# Microcontroller_and_UI.net
KiCad netlist of a schematic drawn in Altium Designer
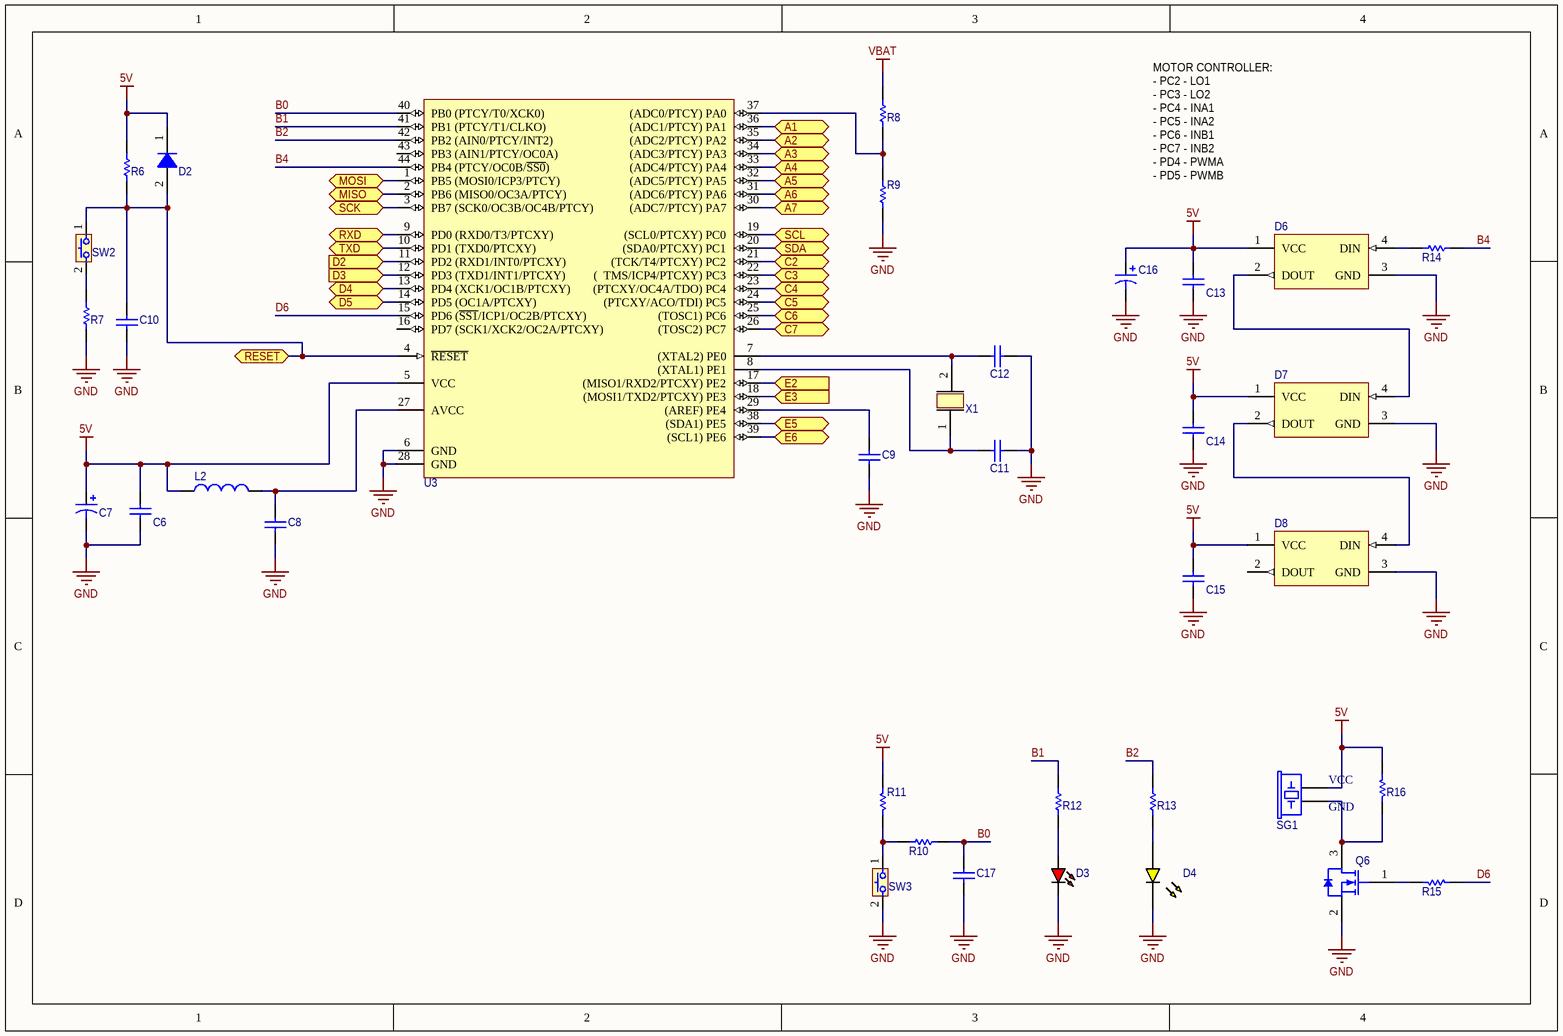
[diagram p0: Microcontroller and UI.SchDoc]

(export (version "E")
  (design (tool "Eeschema 10.0.6"))
  (components
    (comp (ref "C6")
      (value "Kemet C1206C104K5RACAUTO")
      (footprint "CAPC3216X88X50ML20T25")
      (description "Cap Ceramic 0.1uF 50V X7R 10% SMD 1206 125C Plastic T/R")
      (fields (field (name "MANUFACTURER PART NUMBER") "C1206C104K5RACAUTO"))
      (libsource (lib "Octopart library") (part "CAP-2"))
    )
    (comp (ref "C7")
      (value "Cap Pol2")
      (footprint "PCB-2utroa4rb2vd9is4ckmk-1")
      (description "Cap Tant 10UF 10% 16V 2312")
      (libsource (lib "Octopart library") (part "SYM-bf7b7726339260bc-1"))
    )
    (comp (ref "C8")
      (value "Kemet C1206C104K5RACAUTO")
      (footprint "CAPC3216X88X50ML20T25")
      (description "Cap Ceramic 0.1uF 50V X7R 10% SMD 1206 125C Plastic T/R")
      (fields (field (name "MANUFACTURER PART NUMBER") "C1206C104K5RACAUTO"))
      (libsource (lib "CommunityVault") (part "CAP-2"))
    )
    (comp (ref "C9")
      (value "Kemet C1206C104K5RACAUTO")
      (footprint "CAPC3216X88X50ML20T25")
      (description "Cap Ceramic 0.1uF 50V X7R 10% SMD 1206 125C Plastic T/R")
      (fields (field (name "MANUFACTURER PART NUMBER") "C1206C104K5RACAUTO"))
      (libsource (lib "CommunityVault") (part "CAP-2"))
    )
    (comp (ref "C10")
      (value "Kemet C1206C104K5RACAUTO")
      (footprint "CAPC3216X88X50ML20T25")
      (description "Cap Ceramic 0.1uF 50V X7R 10% SMD 1206 125C Plastic T/R")
      (fields (field (name "MANUFACTURER PART NUMBER") "C1206C104K5RACAUTO"))
      (libsource (lib "CommunityVault") (part "CAP-2"))
    )
    (comp (ref "C11")
      (value "Kemet C1206C220K5GACTU")
      (footprint "CAPC3216X88X50LL20T25")
      (fields (field (name "MANUFACTURER PART NUMBER") "C1206C220K5GACTU"))
      (libsource (lib "Octopart library") (part "CAP-2"))
    )
    (comp (ref "C12")
      (value "Kemet C1206C220K5GACTU")
      (footprint "CAPC3216X88X50LL20T25")
      (fields (field (name "MANUFACTURER PART NUMBER") "C1206C220K5GACTU"))
      (libsource (lib "Octopart library") (part "CAP-2"))
    )
    (comp (ref "C13")
      (value "Kemet C1206C104K5RACAUTO")
      (footprint "CAPC3216X88X50ML20T25")
      (description "Cap Ceramic 0.1uF 50V X7R 10% SMD 1206 125C Plastic T/R")
      (fields (field (name "MANUFACTURER PART NUMBER") "C1206C104K5RACAUTO"))
      (libsource (lib "CommunityVault") (part "CAP-2"))
    )
    (comp (ref "C14")
      (value "Kemet C1206C104K5RACAUTO")
      (footprint "CAPC3216X88X50ML20T25")
      (description "Cap Ceramic 0.1uF 50V X7R 10% SMD 1206 125C Plastic T/R")
      (fields (field (name "MANUFACTURER PART NUMBER") "C1206C104K5RACAUTO"))
      (libsource (lib "CommunityVault") (part "CAP-2"))
    )
    (comp (ref "C15")
      (value "Kemet C1206C104K5RACAUTO")
      (footprint "CAPC3216X88X50ML20T25")
      (description "Cap Ceramic 0.1uF 50V X7R 10% SMD 1206 125C Plastic T/R")
      (fields (field (name "MANUFACTURER PART NUMBER") "C1206C104K5RACAUTO"))
      (libsource (lib "CommunityVault") (part "CAP-2"))
    )
    (comp (ref "C16")
      (value "Panasonic EEEFK1C101P")
      (footprint "PCB-bxqn8ynar2jwyklg28q2-1")
      (description "Cap Aluminum Lytic 100uF 16V 20% (6.3 X 5.8mm) SMD 240mA 2000h 105°C Automotive T/R")
      (fields (field (name "MANUFACTURER PART NUMBER") "EEEFK1C101P"))
      (libsource (lib "Octopart library") (part "SYM-6d97a4db90fcb250-1"))
    )
    (comp (ref "C17")
      (value "Kemet C1206C104K5RACAUTO")
      (footprint "CAPC3216X88X50ML20T25")
      (description "Cap Ceramic 0.1uF 50V X7R 10% SMD 1206 125C Plastic T/R")
      (fields (field (name "MANUFACTURER PART NUMBER") "C1206C104K5RACAUTO"))
      (libsource (lib "CommunityVault") (part "CAP-2"))
    )
    (comp (ref "D2")
      (value "Fairchild Semiconductor FDLL4148")
      (footprint "LL-34_AP455")
      (description "Fairchild")
      (fields (field (name "MANUFACTURER PART NUMBER") "FDLL4148"))
      (libsource (lib "Octopart library") (part "DIODE-C1A2-2"))
    )
    (comp (ref "D3")
      (value "Lite-On LTST-C170KRKT")
      (footprint "PCB-7utjwvdtdw1v8scx5ylt-1")
      (description "Red 2 x 1.25 x 1.1 mm 130° Water Clear 54 mcd 2 V LED Surface Mount")
      (fields (field (name "MANUFACTURER PART NUMBER") "LTST-C170KRKT"))
      (libsource (lib "Octopart library") (part "SYM-1d24d4265bb4c2e3-2"))
    )
    (comp (ref "D4")
      (value "Lite-On LTST-C170KSKT")
      (footprint "PCB-3srso9uc5heegaq4ztu4-1")
      (description "Yellow 2 x 1.25 x 1.1 mm 130° Water Clear 112 mcd 1.8 V LED Surface Mount")
      (libsource (lib "Octopart library") (part "SYM-053ccc3e43addafb-1"))
    )
    (comp (ref "D6")
      (value "TE-1981584-1")
      (footprint "PCB-20395447-2")
      (description "INTELLIGENT CONTROL LED without centered Pad")
      (libsource (lib "Octopart library") (part "TE-1981584-1"))
    )
    (comp (ref "D7")
      (value "TE-1981584-1")
      (footprint "PCB-20395447-2")
      (description "INTELLIGENT CONTROL LED without centered Pad")
      (libsource (lib "Octopart library") (part "TE-1981584-1"))
    )
    (comp (ref "D8")
      (value "TE-1981584-1")
      (footprint "PCB-20395447-2")
      (description "INTELLIGENT CONTROL LED without centered Pad")
      (libsource (lib "Octopart library") (part "TE-1981584-1"))
    )
    (comp (ref "L2")
      (value "Bourns CM453232-100KL")
      (footprint "PCB-sj0d1m6kkfqzu57ryeks-1")
      (fields (field (name "MANUFACTURER PART NUMBER") "CM453232-100KL"))
      (libsource (lib "Octopart library") (part "SYM-f812311a91b727d5-1"))
    )
    (comp (ref "Q6")
      (value "SYM-ec4d21f6be82338a-2")
      (footprint "PCB-fnvh88uh0gwuonmuoobt-1")
      (fields (field (name "MANUFACTURER PART NUMBER") "BSS138P,215"))
      (libsource (lib "Octopart library") (part "SYM-ec4d21f6be82338a-2"))
    )
    (comp (ref "R6")
      (value "Vishay CRCW12064K70FKEA")
      (footprint "1206")
      (description "RES SMD 4.7K OHM 1% 1/4W 1206")
      (fields (field (name "MANUFACTURER PART NUMBER") "CRCW12064K70FKEA"))
      (libsource (lib "Octopart library") (part "CRCW12064K70FKEA"))
    )
    (comp (ref "R7")
      (value "Vishay CRCW1206330RFKEA")
      (footprint "PCB-iffx3kyo1buszuhrbsyd-1")
      (description "Res RES SMD 330 OHM 1% 1/4W 1206")
      (libsource (lib "Octopart library") (part "SYM-5f6d9438d73080aa-2"))
    )
    (comp (ref "R8")
      (value "Vishay CRCW12064K70FKEA")
      (footprint "1206")
      (description "RES SMD 4.7K OHM 1% 1/4W 1206")
      (fields (field (name "MANUFACTURER PART NUMBER") "CRCW12064K70FKEA"))
      (libsource (lib "Octopart library") (part "CRCW12064K70FKEA"))
    )
    (comp (ref "R9")
      (value "Vishay Dale CRCW12067K50FKTA")
      (footprint "RESC3216X60X45ML10T20")
      (description "RES SMD 7.5K OHM 1% 1/4W 1206")
      (fields (field (name "MANUFACTURER PART NUMBER") "CRCW12067K50FKTA"))
      (libsource (lib "Octopart library") (part "RES-2"))
    )
    (comp (ref "R10")
      (value "Vishay Dale CRCW12061K00FKEB")
      (footprint "RESC3216X60X45ML10T20")
      (description "Thick Film Resistors - SMD 1/4watt 1Kohms 1%")
      (fields (field (name "MANUFACTURER PART NUMBER") "CRCW12061K00FKEB"))
      (libsource (lib "Octopart library") (part "RES-2"))
    )
    (comp (ref "R11")
      (value "Res1")
      (footprint "PCB-r93x9swl7vzrlon1kcic-1")
      (description "Res Thick Film 1206 10K Ohm 1% 1/4W ±100ppm/°C Molded SMD SMD Paper T/R")
      (fields (field (name "MANUFACTURER PART NUMBER") "CRCW120610K0FKTA"))
      (libsource (lib "Octopart library") (part "SYM-1d37d65bd2a0c2f0-1"))
    )
    (comp (ref "R12")
      (value "Vishay Dale CRCW12061K00FKEB")
      (footprint "RESC3216X60X45ML10T20")
      (description "Thick Film Resistors - SMD 1/4watt 1Kohms 1%")
      (fields (field (name "MANUFACTURER PART NUMBER") "CRCW12061K00FKEB"))
      (libsource (lib "Octopart library") (part "RES-2"))
    )
    (comp (ref "R13")
      (value "Vishay Dale CRCW12061K00FKEB")
      (footprint "RESC3216X60X45ML10T20")
      (description "Thick Film Resistors - SMD 1/4watt 1Kohms 1%")
      (fields (field (name "MANUFACTURER PART NUMBER") "CRCW12061K00FKEB"))
      (libsource (lib "Octopart library") (part "RES-2"))
    )
    (comp (ref "R14")
      (value "Vishay CRCW1206330RFKEA")
      (footprint "PCB-iffx3kyo1buszuhrbsyd-1")
      (description "Res RES SMD 330 OHM 1% 1/4W 1206")
      (libsource (lib "Octopart library") (part "SYM-5f6d9438d73080aa-2"))
    )
    (comp (ref "R15")
      (value "Res1")
      (footprint "PCB-r93x9swl7vzrlon1kcic-1")
      (description "Res Thick Film 1206 10K Ohm 1% 1/4W ±100ppm/°C Molded SMD SMD Paper T/R")
      (fields (field (name "MANUFACTURER PART NUMBER") "CRCW120610K0FKTA"))
      (libsource (lib "Octopart library") (part "SYM-1d37d65bd2a0c2f0-1"))
    )
    (comp (ref "R16")
      (value "Res1")
      (footprint "PCB-r93x9swl7vzrlon1kcic-1")
      (description "Res Thick Film 1206 10K Ohm 1% 1/4W ±100ppm/°C Molded SMD SMD Paper T/R")
      (fields (field (name "MANUFACTURER PART NUMBER") "CRCW120610K0FKTA"))
      (libsource (lib "Octopart library") (part "SYM-1d37d65bd2a0c2f0-1"))
    )
    (comp (ref "SG1")
      (value "SYM-4a3d82e3cb5995fa-1")
      (footprint "PCB-8mby96szrz0u2nyklaj3-1")
      (description "Sound transducer: piezo alarm; with built-in generator; THT")
      (libsource (lib "Octopart library") (part "SYM-4a3d82e3cb5995fa-1"))
    )
    (comp (ref "SW2")
      (value "KMR231NGLFS")
      (footprint "PCB-073utuz7vwed4h5iqcvq-1")
      (description "Switch Tactile N.O. SPST Button Gull Wing 0.05A 32VDC 1VA 150000Cycles 3N SMD Automotive T/R")
      (libsource (lib "Octopart library") (part "SYM-ffd536b079f82012-1"))
    )
    (comp (ref "SW3")
      (value "KMR231NGLFS")
      (footprint "PCB-073utuz7vwed4h5iqcvq-1")
      (description "Switch Tactile N.O. SPST Button Gull Wing 0.05A 32VDC 1VA 150000Cycles 3N SMD Automotive T/R")
      (libsource (lib "Octopart library") (part "SYM-ffd536b079f82012-1"))
    )
    (comp (ref "U3")
      (value "SYM-89d944712a27561e-1")
      (footprint "PCB-mnk8bms7mnnc6ivbcvvg-1")
      (description "AVR microcontroller; EEPROM: 1kB; SRAM: 2kB; Flash: 32kB; TQFP44")
      (libsource (lib "CommunityVault") (part "SYM-89d944712a27561e-1"))
    )
    (comp (ref "X1")
      (value "Multicomp HC49S-16-30-50-70-30-ATF")
      (footprint "PCB-g1xa0dtupmw0r2hsib2r-1")
      (libsource (lib "CommunityVault") (part "CMP-c0ad0924a56a1f6a-3"))
    )
  )
  (nets
    (net (code "1") (name "/A1") (class "Default")
      (node (ref "U3") (pin "36") (pinfunction "(ADC1/PTCY)_PA1_36") (pintype "bidirectional"))
    )
    (net (code "2") (name "/A2") (class "Default")
      (node (ref "U3") (pin "35") (pinfunction "(ADC2/PTCY)_PA2_35") (pintype "bidirectional"))
    )
    (net (code "3") (name "/A3") (class "Default")
      (node (ref "U3") (pin "34") (pinfunction "(ADC3/PTCY)_PA3_34") (pintype "bidirectional"))
    )
    (net (code "4") (name "/A4") (class "Default")
      (node (ref "U3") (pin "33") (pinfunction "(ADC4/PTCY)_PA4_33") (pintype "bidirectional"))
    )
    (net (code "5") (name "/A5") (class "Default")
      (node (ref "U3") (pin "32") (pinfunction "(ADC5/PTCY)_PA5_32") (pintype "bidirectional"))
    )
    (net (code "6") (name "/A6") (class "Default")
      (node (ref "U3") (pin "31") (pinfunction "(ADC6/PTCY)_PA6_31") (pintype "bidirectional"))
    )
    (net (code "7") (name "/A7") (class "Default")
      (node (ref "U3") (pin "30") (pinfunction "(ADC7/PTCY)_PA7_30") (pintype "bidirectional"))
    )
    (net (code "8") (name "/B0") (class "Default")
      (node (ref "C17") (pin "2") (pinfunction "2_2") (pintype "passive"))
      (node (ref "R10") (pin "2") (pinfunction "2_2") (pintype "passive"))
      (node (ref "U3") (pin "40") (pinfunction "PB0_(PTCY/T0/XCK0)_40") (pintype "bidirectional"))
    )
    (net (code "9") (name "/B1") (class "Default")
      (node (ref "R12") (pin "2") (pinfunction "2_2") (pintype "passive"))
      (node (ref "U3") (pin "41") (pinfunction "PB1_(PTCY/T1/CLKO)_41") (pintype "bidirectional"))
    )
    (net (code "10") (name "/B2") (class "Default")
      (node (ref "R13") (pin "2") (pinfunction "2_2") (pintype "passive"))
      (node (ref "U3") (pin "42") (pinfunction "PB2_(AIN0/PTCY/INT2)_42") (pintype "bidirectional"))
    )
    (net (code "11") (name "/B4") (class "Default")
      (node (ref "R14") (pin "1") (pinfunction "1_1") (pintype "passive"))
      (node (ref "U3") (pin "44") (pinfunction "PB4_(PTCY/OC0B/~{SS0})_44") (pintype "bidirectional"))
    )
    (net (code "12") (name "/C2") (class "Default")
      (node (ref "U3") (pin "21") (pinfunction "(TCK/T4/PTCXY)_PC2_21") (pintype "bidirectional"))
    )
    (net (code "13") (name "/C3") (class "Default")
      (node (ref "U3") (pin "22") (pinfunction "(__TMS/ICP4/PTCXY)_PC3_22") (pintype "bidirectional"))
    )
    (net (code "14") (name "/C4") (class "Default")
      (node (ref "U3") (pin "23") (pinfunction "(PTCXY/OC4A/TDO)_PC4_23") (pintype "bidirectional"))
    )
    (net (code "15") (name "/C5") (class "Default")
      (node (ref "U3") (pin "24") (pinfunction "(PTCXY/ACO/TDI)_PC5_24") (pintype "bidirectional"))
    )
    (net (code "16") (name "/C6") (class "Default")
      (node (ref "U3") (pin "25") (pinfunction "(TOSC1)_PC6_25") (pintype "bidirectional"))
    )
    (net (code "17") (name "/C7") (class "Default")
      (node (ref "U3") (pin "26") (pinfunction "(TOSC2)_PC7_26") (pintype "bidirectional"))
    )
    (net (code "18") (name "/D2") (class "Default")
      (node (ref "U3") (pin "11") (pinfunction "PD2_(RXD1/INT0/PTCXY)_11") (pintype "bidirectional"))
    )
    (net (code "19") (name "/D3") (class "Default")
      (node (ref "U3") (pin "12") (pinfunction "PD3_(TXD1/INT1/PTCXY)_12") (pintype "bidirectional"))
    )
    (net (code "20") (name "/D4") (class "Default")
      (node (ref "U3") (pin "13") (pinfunction "PD4_(XCK1/OC1B/PTCXY)_13") (pintype "bidirectional"))
    )
    (net (code "21") (name "/D5") (class "Default")
      (node (ref "U3") (pin "14") (pinfunction "PD5_(OC1A/PTCXY)_14") (pintype "bidirectional"))
    )
    (net (code "22") (name "/D6") (class "Default")
      (node (ref "R15") (pin "2") (pinfunction "2_2") (pintype "passive"))
      (node (ref "U3") (pin "15") (pinfunction "PD6_(~{SS1}/ICP1/OC2B/PTCXY)_15") (pintype "bidirectional"))
    )
    (net (code "23") (name "/E2") (class "Default")
      (node (ref "U3") (pin "17") (pinfunction "(MISO1/RXD2/PTCXY)_PE2_17") (pintype "bidirectional"))
    )
    (net (code "24") (name "/E3") (class "Default")
      (node (ref "U3") (pin "18") (pinfunction "(MOSI1/TXD2/PTCXY)_PE3_18") (pintype "bidirectional"))
    )
    (net (code "25") (name "/E5") (class "Default")
      (node (ref "U3") (pin "38") (pinfunction "(SDA1)_PE5_38") (pintype "bidirectional"))
    )
    (net (code "26") (name "/E6") (class "Default")
      (node (ref "U3") (pin "39") (pinfunction "(SCL1)_PE6_39") (pintype "bidirectional"))
    )
    (net (code "27") (name "/MISO") (class "Default")
      (node (ref "U3") (pin "2") (pinfunction "PB6_(MISO0/OC3A/PTCY)_2") (pintype "bidirectional"))
    )
    (net (code "28") (name "/MOSI") (class "Default")
      (node (ref "U3") (pin "1") (pinfunction "PB5_(MOSI0/ICP3/PTCY)_1") (pintype "bidirectional"))
    )
    (net (code "29") (name "/RESET") (class "Default")
      (node (ref "C10") (pin "2") (pinfunction "2_2") (pintype "passive"))
      (node (ref "D2") (pin "2") (pinfunction "ANODE_2") (pintype "passive"))
      (node (ref "R6") (pin "2") (pinfunction "2_2") (pintype "passive"))
      (node (ref "SW2") (pin "1") (pinfunction "1_1") (pintype "passive"))
      (node (ref "U3") (pin "4") (pinfunction "~{RESET}_4") (pintype "input"))
    )
    (net (code "30") (name "/RXD") (class "Default")
      (node (ref "U3") (pin "9") (pinfunction "PD0_(RXD0/T3/PTCXY)_9") (pintype "bidirectional"))
    )
    (net (code "31") (name "/SCK") (class "Default")
      (node (ref "U3") (pin "3") (pinfunction "PB7_(SCK0/OC3B/OC4B/PTCY)_3") (pintype "bidirectional"))
    )
    (net (code "32") (name "/SCL") (class "Default")
      (node (ref "U3") (pin "19") (pinfunction "(SCL0/PTCXY)_PC0_19") (pintype "bidirectional"))
    )
    (net (code "33") (name "/SDA") (class "Default")
      (node (ref "U3") (pin "20") (pinfunction "(SDA0/PTCXY)_PC1_20") (pintype "bidirectional"))
    )
    (net (code "34") (name "/TXD") (class "Default")
      (node (ref "U3") (pin "10") (pinfunction "PD1_(TXD0/PTCXY)_10") (pintype "bidirectional"))
    )
    (net (code "35") (name "5V") (class "Default")
      (node (ref "C13") (pin "1") (pinfunction "1_1") (pintype "passive"))
      (node (ref "C14") (pin "1") (pinfunction "1_1") (pintype "passive"))
      (node (ref "C15") (pin "1") (pinfunction "1_1") (pintype "passive"))
      (node (ref "C16") (pin "1") (pinfunction "1_1") (pintype "passive"))
      (node (ref "C6") (pin "2") (pinfunction "2_2") (pintype "passive"))
      (node (ref "C7") (pin "1") (pinfunction "1_1") (pintype "passive"))
      (node (ref "D2") (pin "1") (pinfunction "CATHODE_1") (pintype "passive"))
      (node (ref "D6") (pin "1") (pinfunction "VCC_1") (pintype "power_in"))
      (node (ref "D7") (pin "1") (pinfunction "VCC_1") (pintype "power_in"))
      (node (ref "D8") (pin "1") (pinfunction "VCC_1") (pintype "power_in"))
      (node (ref "L2") (pin "1") (pinfunction "1_1") (pintype "passive"))
      (node (ref "R11") (pin "1") (pinfunction "1_1") (pintype "passive"))
      (node (ref "R16") (pin "2") (pinfunction "2_2") (pintype "passive"))
      (node (ref "R6") (pin "1") (pinfunction "1_1") (pintype "passive"))
      (node (ref "SG1") (pin "0") (pinfunction "+_0") (pintype "passive"))
      (node (ref "U3") (pin "5") (pinfunction "VCC_5") (pintype "power_in"))
    )
    (net (code "36") (name "GND") (class "Default")
      (node (ref "C10") (pin "1") (pinfunction "1_1") (pintype "passive"))
      (node (ref "C11") (pin "1") (pinfunction "1_1") (pintype "passive"))
      (node (ref "C12") (pin "1") (pinfunction "1_1") (pintype "passive"))
      (node (ref "C13") (pin "2") (pinfunction "2_2") (pintype "passive"))
      (node (ref "C14") (pin "2") (pinfunction "2_2") (pintype "passive"))
      (node (ref "C15") (pin "2") (pinfunction "2_2") (pintype "passive"))
      (node (ref "C16") (pin "2") (pinfunction "2_2") (pintype "passive"))
      (node (ref "C17") (pin "1") (pinfunction "1_1") (pintype "passive"))
      (node (ref "C6") (pin "1") (pinfunction "1_1") (pintype "passive"))
      (node (ref "C7") (pin "2") (pinfunction "2_2") (pintype "passive"))
      (node (ref "C8") (pin "1") (pinfunction "1_1") (pintype "passive"))
      (node (ref "C9") (pin "1") (pinfunction "1_1") (pintype "passive"))
      (node (ref "D3") (pin "2") (pinfunction "K_2") (pintype "passive"))
      (node (ref "D4") (pin "2") (pinfunction "K_2") (pintype "passive"))
      (node (ref "D6") (pin "3") (pinfunction "GND_3") (pintype "power_in"))
      (node (ref "D7") (pin "3") (pinfunction "GND_3") (pintype "power_in"))
      (node (ref "D8") (pin "3") (pinfunction "GND_3") (pintype "power_in"))
      (node (ref "Q6") (pin "2") (pinfunction "S_2") (pintype "passive"))
      (node (ref "R7") (pin "2") (pinfunction "2_2") (pintype "passive"))
      (node (ref "R9") (pin "2") (pinfunction "2_2") (pintype "passive"))
      (node (ref "SW3") (pin "2") (pinfunction "2_2") (pintype "passive"))
      (node (ref "U3") (pin "28") (pinfunction "GND_28") (pintype "power_in"))
      (node (ref "U3") (pin "6") (pinfunction "GND_6") (pintype "power_in"))
    )
    (net (code "37") (name "Net-(D3-A)") (class "Default")
      (node (ref "D3") (pin "1") (pinfunction "A_1") (pintype "passive"))
      (node (ref "R12") (pin "1") (pinfunction "1_1") (pintype "passive"))
    )
    (net (code "38") (name "Net-(D4-A)") (class "Default")
      (node (ref "D4") (pin "1") (pinfunction "A_1") (pintype "passive"))
      (node (ref "R13") (pin "1") (pinfunction "1_1") (pintype "passive"))
    )
    (net (code "39") (name "Net-(D6-DIN)") (class "Default")
      (node (ref "D6") (pin "4") (pinfunction "DIN_4") (pintype "input"))
      (node (ref "R14") (pin "2") (pinfunction "2_2") (pintype "passive"))
    )
    (net (code "40") (name "Net-(D6-DOUT)") (class "Default")
      (node (ref "D6") (pin "2") (pinfunction "DOUT_2") (pintype "output"))
      (node (ref "D7") (pin "4") (pinfunction "DIN_4") (pintype "input"))
    )
    (net (code "41") (name "Net-(D7-DOUT)") (class "Default")
      (node (ref "D7") (pin "2") (pinfunction "DOUT_2") (pintype "output"))
      (node (ref "D8") (pin "4") (pinfunction "DIN_4") (pintype "input"))
    )
    (net (code "42") (name "Net-(Q6-D)") (class "Default")
      (node (ref "Q6") (pin "3") (pinfunction "D_3") (pintype "passive"))
      (node (ref "R16") (pin "1") (pinfunction "1_1") (pintype "passive"))
      (node (ref "SG1") (pin "1") (pinfunction "-_1") (pintype "passive"))
    )
    (net (code "43") (name "Net-(Q6-G)") (class "Default")
      (node (ref "Q6") (pin "1") (pinfunction "G_1") (pintype "passive"))
      (node (ref "R15") (pin "1") (pinfunction "1_1") (pintype "passive"))
    )
    (net (code "44") (name "Net-(R7-Pad1)") (class "Default")
      (node (ref "R7") (pin "1") (pinfunction "1_1") (pintype "passive"))
      (node (ref "SW2") (pin "2") (pinfunction "2_2") (pintype "passive"))
    )
    (net (code "45") (name "Net-(R10-Pad1)") (class "Default")
      (node (ref "R10") (pin "1") (pinfunction "1_1") (pintype "passive"))
      (node (ref "R11") (pin "2") (pinfunction "2_2") (pintype "passive"))
      (node (ref "SW3") (pin "1") (pinfunction "1_1") (pintype "passive"))
    )
    (net (code "46") (name "Net-(U3-(ADC0{slash}PTCY)_PA0)") (class "Default")
      (node (ref "R8") (pin "1") (pinfunction "1_1") (pintype "passive"))
      (node (ref "R9") (pin "1") (pinfunction "1_1") (pintype "passive"))
      (node (ref "U3") (pin "37") (pinfunction "(ADC0/PTCY)_PA0_37") (pintype "bidirectional"))
    )
    (net (code "47") (name "Net-(U3-(AREF)_PE4)") (class "Default")
      (node (ref "C9") (pin "2") (pinfunction "2_2") (pintype "passive"))
      (node (ref "U3") (pin "29") (pinfunction "(AREF)_PE4_29") (pintype "bidirectional"))
    )
    (net (code "48") (name "Net-(U3-(XTAL1)_PE1)") (class "Default")
      (node (ref "C11") (pin "2") (pinfunction "2_2") (pintype "passive"))
      (node (ref "U3") (pin "8") (pinfunction "(XTAL1)_PE1_8") (pintype "passive"))
      (node (ref "X1") (pin "1") (pinfunction "1_1") (pintype "passive"))
    )
    (net (code "49") (name "Net-(U3-(XTAL2)_PE0)") (class "Default")
      (node (ref "C12") (pin "2") (pinfunction "2_2") (pintype "passive"))
      (node (ref "U3") (pin "7") (pinfunction "(XTAL2)_PE0_7") (pintype "passive"))
      (node (ref "X1") (pin "2") (pinfunction "2_2") (pintype "passive"))
    )
    (net (code "50") (name "Net-(U3-AVCC)") (class "Default")
      (node (ref "C8") (pin "2") (pinfunction "2_2") (pintype "passive"))
      (node (ref "L2") (pin "2") (pinfunction "2_2") (pintype "passive"))
      (node (ref "U3") (pin "27") (pinfunction "AVCC_27") (pintype "power_in"))
    )
    (net (code "51") (name "VBAT") (class "Default")
      (node (ref "R8") (pin "2") (pinfunction "2_2") (pintype "passive"))
    )
    (net (code "52") (name "unconnected-(D8-DOUT-Pad2)") (class "Default")
      (node (ref "D8") (pin "2") (pinfunction "DOUT_2") (pintype "output"))
    )
    (net (code "53") (name "unconnected-(U3-PB3_(AIN1{slash}PTCY{slash}OC0A)-Pad43)") (class "Default")
      (node (ref "U3") (pin "43") (pinfunction "PB3_(AIN1/PTCY/OC0A)_43") (pintype "bidirectional"))
    )
    (net (code "54") (name "unconnected-(U3-PD7_(SCK1{slash}XCK2{slash}OC2A{slash}PTCXY)-Pad16)") (class "Default")
      (node (ref "U3") (pin "16") (pinfunction "PD7_(SCK1/XCK2/OC2A/PTCXY)_16") (pintype "bidirectional"))
    )
  )
)
